# 800U-R3N3_IB_LED_V1_0.net
KiCad netlist of a schematic drawn in Altium Designer
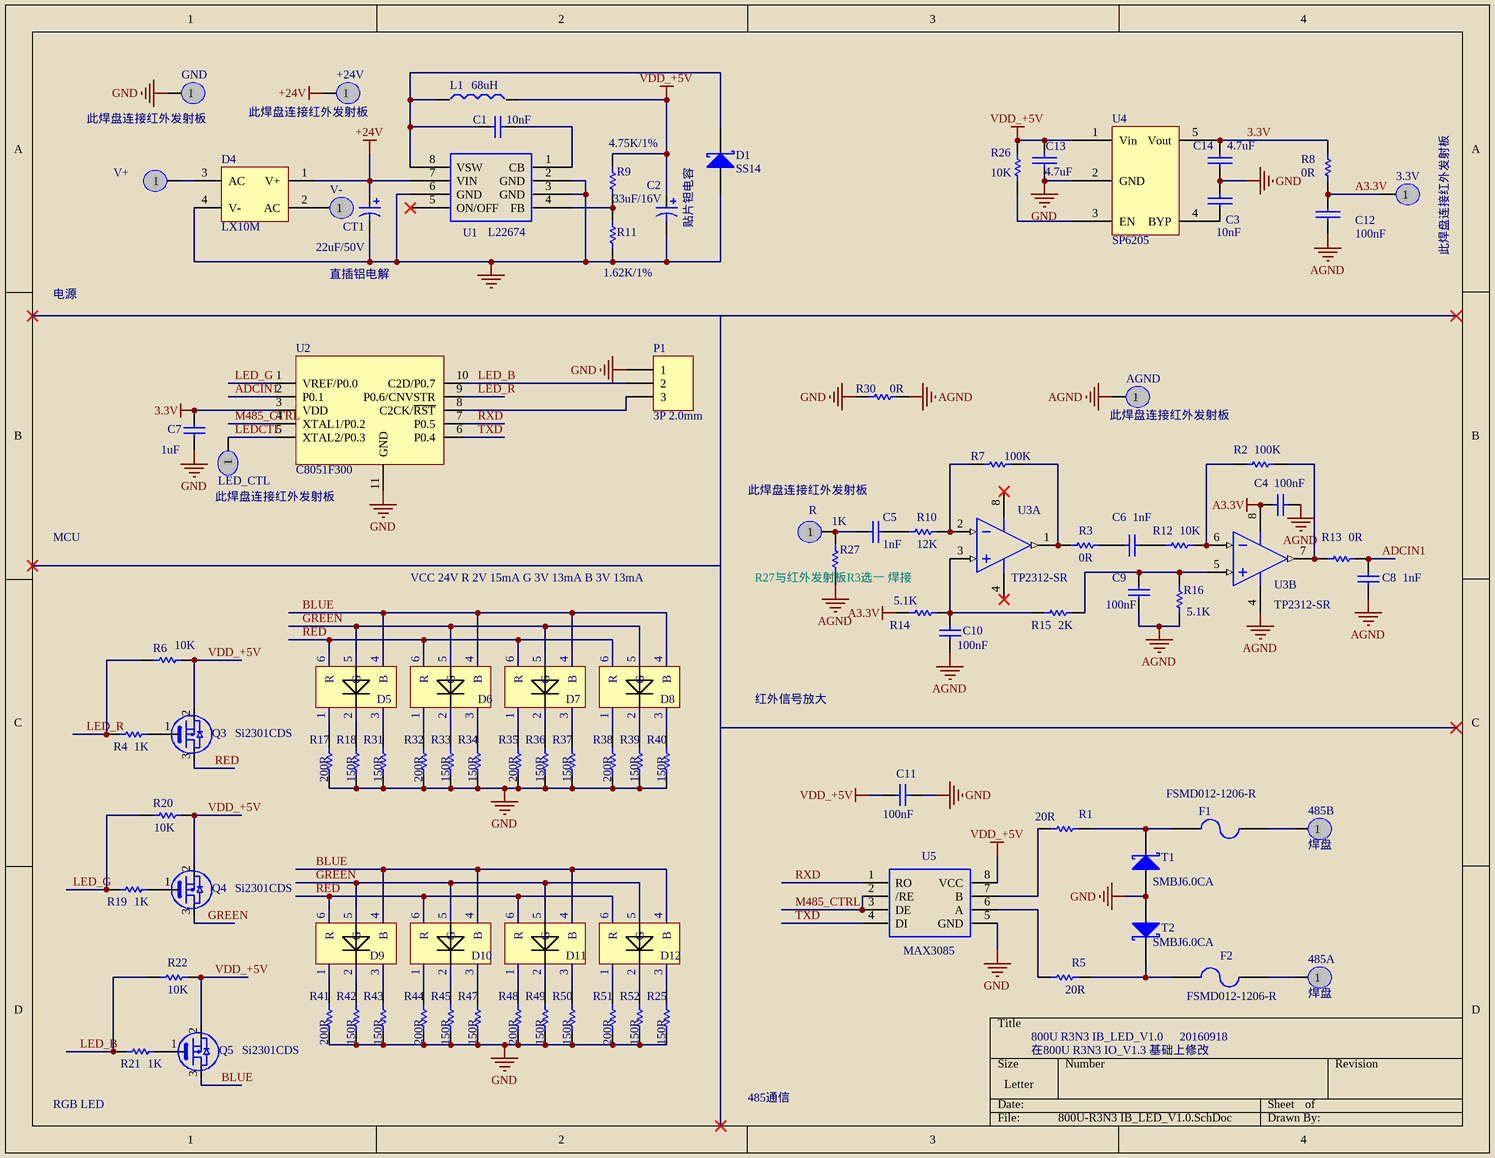
[diagram p0: 800U-R3N3 IB_LED_V1.0.SchDoc]

(export (version "E")
  (design (tool "Eeschema 10.0.6"))
  (components
    (comp (ref "+24V")
      (value "~")
      (footprint "HOLE_SMD")
      (fields (field (name "ALTIUM_UNNAMED_1") "此焊盘连接红外发射板"))
      (libsource (lib "MODBUS_V1.0") (part "焊盘"))
    )
    (comp (ref "3.3V")
      (value "~")
      (footprint "HOLE_SMD")
      (fields (field (name "ALTIUM_UNNAMED_1") "此焊盘连接红外发射板"))
      (libsource (lib "MODBUS_V1.0") (part "焊盘"))
    )
    (comp (ref "485A") (value "焊盘") (footprint "HOLE_SMD") (libsource (lib "MODBUS_V1.0") (part "焊盘")))
    (comp (ref "485B") (value "焊盘") (footprint "HOLE_SMD") (libsource (lib "MODBUS_V1.0") (part "焊盘")))
    (comp (ref "AGND")
      (value "~")
      (footprint "HOLE_SMD")
      (fields (field (name "ALTIUM_UNNAMED_1") "此焊盘连接红外发射板"))
      (libsource (lib "MODBUS_V1.0") (part "焊盘"))
    )
    (comp (ref "C1")
      (value "10nF")
      (footprint "C0603")
      (description "Capacitor")
      (fields (field (name "PUBLISHER") "Altium Limited"))
      (libsource (lib "*") (part "Cap"))
    )
    (comp (ref "C2")
      (value "33uF/16V")
      (footprint "CT3528")
      (description "Polarized Capacitor (Radial)")
      (fields (field (name "KIND") "贴片钽电容"))
      (libsource (lib "*") (part "Cap Pol1"))
    )
    (comp (ref "C3")
      (value "10nF")
      (footprint "C0603")
      (description "Capacitor")
      (libsource (lib "*") (part "CAP"))
    )
    (comp (ref "C4")
      (value "100nF")
      (footprint "C0603")
      (description "Capacitor")
      (fields (field (name "PUBLISHER") "Altium Limited"))
      (libsource (lib "TMJD1.0") (part "Cap"))
    )
    (comp (ref "C5")
      (value "1nF")
      (footprint "C0603")
      (description "Capacitor")
      (fields (field (name "PUBLISHER") "Altium Limited"))
      (libsource (lib "TMJD1.0") (part "Cap"))
    )
    (comp (ref "C6")
      (value "1nF")
      (footprint "C0603")
      (description "Capacitor")
      (fields (field (name "PUBLISHER") "Altium Limited"))
      (libsource (lib "TMJD1.0") (part "Cap"))
    )
    (comp (ref "C7")
      (value "1uF")
      (footprint "C0603")
      (description "贴片电容")
      (fields (field (name "PUBLISHER") "Altium Limited"))
      (libsource (lib "TMJD1.0") (part "Cap"))
    )
    (comp (ref "C8")
      (value "1nF")
      (footprint "C0603")
      (description "Capacitor")
      (fields (field (name "PUBLISHER") "Altium Limited"))
      (libsource (lib "TMJD1.0") (part "Cap"))
    )
    (comp (ref "C9")
      (value "100nF")
      (footprint "C0603")
      (description "Capacitor")
      (fields (field (name "PUBLISHER") "Altium Limited"))
      (libsource (lib "TMJD1.0") (part "Cap"))
    )
    (comp (ref "C10")
      (value "100nF")
      (footprint "C0603")
      (description "Capacitor")
      (fields (field (name "PUBLISHER") "Altium Limited"))
      (libsource (lib "TMJD1.0") (part "Cap"))
    )
    (comp (ref "C11")
      (value "100nF")
      (footprint "C0603")
      (description "贴片陶瓷电容")
      (libsource (lib "Miscellaneous Devices") (part "Cap"))
    )
    (comp (ref "C12")
      (value "100nF")
      (footprint "C0603")
      (description "Capacitor")
      (libsource (lib "*") (part "CAP"))
    )
    (comp (ref "C13")
      (value "4.7uF")
      (footprint "C0603")
      (description "Capacitor")
      (libsource (lib "*") (part "CAP"))
    )
    (comp (ref "C14")
      (value "4.7uF")
      (footprint "C0603")
      (description "Capacitor")
      (libsource (lib "*") (part "CAP"))
    )
    (comp (ref "CT1")
      (value "22uF/50V")
      (footprint "RB0.1")
      (description "Polarized Capacitor (Radial)")
      (fields (field (name "KIND") "直插铝电解"))
      (libsource (lib "*") (part "Cap Pol1"))
    )
    (comp (ref "D1") (value "SS14") (footprint "SMB") (libsource (lib "*") (part "SMBJ6.0CA")))
    (comp (ref "D4")
      (value "LX10M")
      (footprint "桥堆 3.8*3.5")
      (description "贴片桥堆")
      (libsource (lib "Miscellaneous Devices") (part "Bridge2"))
    )
    (comp (ref "D5")
      (value "5050RGB")
      (footprint "5050RGB")
      (description "RBG发光管")
      (libsource (lib "MODBUS_V1.0") (part "5050RGB"))
    )
    (comp (ref "D6")
      (value "5050RGB")
      (footprint "5050RGB")
      (description "RBG发光管")
      (libsource (lib "MODBUS_V1.0") (part "5050RGB"))
    )
    (comp (ref "D7")
      (value "5050RGB")
      (footprint "5050RGB")
      (description "RBG发光管")
      (libsource (lib "MODBUS_V1.0") (part "5050RGB"))
    )
    (comp (ref "D8")
      (value "5050RGB")
      (footprint "5050RGB")
      (description "RBG发光管")
      (libsource (lib "MODBUS_V1.0") (part "5050RGB"))
    )
    (comp (ref "D9")
      (value "5050RGB")
      (footprint "5050RGB")
      (description "RBG发光管")
      (libsource (lib "MODBUS_V1.0") (part "5050RGB"))
    )
    (comp (ref "D10")
      (value "5050RGB")
      (footprint "5050RGB")
      (description "RBG发光管")
      (libsource (lib "MODBUS_V1.0") (part "5050RGB"))
    )
    (comp (ref "D11")
      (value "5050RGB")
      (footprint "5050RGB")
      (description "RBG发光管")
      (libsource (lib "MODBUS_V1.0") (part "5050RGB"))
    )
    (comp (ref "D12")
      (value "5050RGB")
      (footprint "5050RGB")
      (description "RBG发光管")
      (libsource (lib "MODBUS_V1.0") (part "5050RGB"))
    )
    (comp (ref "F1")
      (value "FSMD012-1206-R")
      (footprint "1206")
      (description "可恢复保险丝")
      (libsource (lib "Miscellaneous Devices") (part "Fuse 2"))
    )
    (comp (ref "F2")
      (value "FSMD012-1206-R")
      (footprint "1206")
      (description "可恢复保险丝")
      (libsource (lib "Miscellaneous Devices") (part "Fuse 2"))
    )
    (comp (ref "GND")
      (value "~")
      (footprint "HOLE_SMD")
      (fields (field (name "ALTIUM_UNNAMED_1") "此焊盘连接红外发射板"))
      (libsource (lib "MODBUS_V1.0") (part "焊盘"))
    )
    (comp (ref "L1") (value "68uH") (footprint "L-6X6") (libsource (lib "*") (part "电感")))
    (comp (ref "LED_CTL")
      (value "~")
      (footprint "HOLE_SMD")
      (fields (field (name "ALTIUM_UNNAMED_1") "此焊盘连接红外发射板"))
      (libsource (lib "MODBUS_V1.0") (part "焊盘"))
    )
    (comp (ref "P1")
      (value "3P 2.0mm")
      (footprint "SIP3")
      (description "插座")
      (fields (field (name "PUBLISHER") "Altium Limited"))
      (libsource (lib "Miscellaneous Connectors") (part "MHDR1X3"))
    )
    (comp (ref "Q3")
      (value "Si2301CDS")
      (footprint "SOT-23")
      (description "贴片MOS管")
      (libsource (lib "BATTERY") (part "P-MOSFET"))
    )
    (comp (ref "Q4")
      (value "Si2301CDS")
      (footprint "SOT-23")
      (description "贴片MOS管")
      (libsource (lib "BATTERY") (part "P-MOSFET"))
    )
    (comp (ref "Q5")
      (value "Si2301CDS")
      (footprint "SOT-23")
      (description "贴片MOS管")
      (libsource (lib "BATTERY") (part "P-MOSFET"))
    )
    (comp (ref "R")
      (value "~")
      (footprint "HOLE_SMD")
      (fields (field (name "ALTIUM_UNNAMED_1") "此焊盘连接红外发射板"))
      (libsource (lib "MODBUS_V1.0") (part "焊盘"))
    )
    (comp (ref "R1")
      (value "20R")
      (footprint "2010")
      (description "贴片电阻")
      (libsource (lib "Miscellaneous Devices") (part "Res Semi"))
    )
    (comp (ref "R2")
      (value "100K")
      (footprint "R0603")
      (description "Semiconductor Resistor")
      (libsource (lib "Miscellaneous Devices") (part "Res Semi"))
    )
    (comp (ref "R3")
      (value "0R")
      (footprint "R0603")
      (description "Semiconductor Resistor")
      (libsource (lib "Miscellaneous Devices") (part "Res Semi"))
    )
    (comp (ref "R4")
      (value "1K")
      (footprint "R0603")
      (description "贴片电阻")
      (libsource (lib "Miscellaneous Devices") (part "Res Semi"))
    )
    (comp (ref "R5")
      (value "20R")
      (footprint "2010")
      (description "贴片电阻")
      (libsource (lib "Miscellaneous Devices") (part "Res Semi"))
    )
    (comp (ref "R6")
      (value "10K")
      (footprint "R0603")
      (description "贴片电阻")
      (libsource (lib "Miscellaneous Devices") (part "Res Semi"))
    )
    (comp (ref "R7")
      (value "100K")
      (footprint "R0603")
      (description "Semiconductor Resistor")
      (libsource (lib "Miscellaneous Devices") (part "Res Semi"))
    )
    (comp (ref "R8")
      (value "0R")
      (footprint "R0603")
      (description "Resistor")
      (fields (field (name "PUBLISHER") "Altium Limited"))
      (libsource (lib "*") (part "Res1"))
    )
    (comp (ref "R9")
      (value "4.75K/1%")
      (footprint "R0603")
      (description "Semiconductor Resistor")
      (fields (field (name "PUBLISHER") "Altium Limited"))
      (libsource (lib "*") (part "Res Semi"))
    )
    (comp (ref "R10")
      (value "12K")
      (footprint "R0603")
      (description "Semiconductor Resistor")
      (libsource (lib "Miscellaneous Devices") (part "Res Semi"))
    )
    (comp (ref "R11")
      (value "1.62K/1%")
      (footprint "R0603")
      (description "Semiconductor Resistor")
      (fields (field (name "PUBLISHER") "Altium Limited"))
      (libsource (lib "*") (part "Res Semi"))
    )
    (comp (ref "R12")
      (value "10K")
      (footprint "R0603")
      (description "Semiconductor Resistor")
      (libsource (lib "Miscellaneous Devices") (part "Res Semi"))
    )
    (comp (ref "R13")
      (value "0R")
      (footprint "R0603")
      (description "Semiconductor Resistor")
      (libsource (lib "Miscellaneous Devices") (part "Res Semi"))
    )
    (comp (ref "R14")
      (value "5.1K")
      (footprint "R0603")
      (description "Semiconductor Resistor")
      (libsource (lib "Miscellaneous Devices") (part "Res Semi"))
    )
    (comp (ref "R15")
      (value "2K")
      (footprint "R0603")
      (description "Semiconductor Resistor")
      (libsource (lib "Miscellaneous Devices") (part "Res Semi"))
    )
    (comp (ref "R16")
      (value "5.1K")
      (footprint "R0603")
      (description "Semiconductor Resistor")
      (libsource (lib "Miscellaneous Devices") (part "Res Semi"))
    )
    (comp (ref "R17")
      (value "200R")
      (footprint "0805")
      (description "贴片电阻")
      (libsource (lib "Miscellaneous Devices") (part "Res Semi"))
    )
    (comp (ref "R18")
      (value "150R")
      (footprint "0805")
      (description "贴片电阻")
      (libsource (lib "Miscellaneous Devices") (part "Res Semi"))
    )
    (comp (ref "R19")
      (value "1K")
      (footprint "R0603")
      (description "贴片电阻")
      (libsource (lib "Miscellaneous Devices") (part "Res Semi"))
    )
    (comp (ref "R20")
      (value "10K")
      (footprint "R0603")
      (description "贴片电阻")
      (libsource (lib "Miscellaneous Devices") (part "Res Semi"))
    )
    (comp (ref "R21")
      (value "1K")
      (footprint "R0603")
      (description "贴片电阻")
      (libsource (lib "Miscellaneous Devices") (part "Res Semi"))
    )
    (comp (ref "R22")
      (value "10K")
      (footprint "R0603")
      (description "贴片电阻")
      (libsource (lib "Miscellaneous Devices") (part "Res Semi"))
    )
    (comp (ref "R25")
      (value "150R")
      (footprint "0805")
      (description "贴片电阻")
      (libsource (lib "Miscellaneous Devices") (part "Res Semi"))
    )
    (comp (ref "R26")
      (value "10K")
      (footprint "R0603")
      (description "Resistor")
      (fields (field (name "PUBLISHER") "Altium Limited"))
      (libsource (lib "*") (part "Res1"))
    )
    (comp (ref "R27")
      (value "1K")
      (footprint "R0603")
      (description "Semiconductor Resistor")
      (fields (field (name "ALTIUM_UNNAMED_1") "R27与红外发射板R3选一 焊接"))
      (libsource (lib "Miscellaneous Devices") (part "Res Semi"))
    )
    (comp (ref "R30")
      (value "0R")
      (footprint "R0603")
      (description "Semiconductor Resistor")
      (libsource (lib "Miscellaneous Devices") (part "Res Semi"))
    )
    (comp (ref "R31")
      (value "150R")
      (footprint "0805")
      (description "贴片电阻")
      (libsource (lib "Miscellaneous Devices") (part "Res Semi"))
    )
    (comp (ref "R32")
      (value "200R")
      (footprint "0805")
      (description "贴片电阻")
      (libsource (lib "Miscellaneous Devices") (part "Res Semi"))
    )
    (comp (ref "R33")
      (value "150R")
      (footprint "0805")
      (description "贴片电阻")
      (libsource (lib "Miscellaneous Devices") (part "Res Semi"))
    )
    (comp (ref "R34")
      (value "150R")
      (footprint "0805")
      (description "贴片电阻")
      (libsource (lib "Miscellaneous Devices") (part "Res Semi"))
    )
    (comp (ref "R35")
      (value "200R")
      (footprint "0805")
      (description "贴片电阻")
      (libsource (lib "Miscellaneous Devices") (part "Res Semi"))
    )
    (comp (ref "R36")
      (value "150R")
      (footprint "0805")
      (description "贴片电阻")
      (libsource (lib "Miscellaneous Devices") (part "Res Semi"))
    )
    (comp (ref "R37")
      (value "150R")
      (footprint "0805")
      (description "贴片电阻")
      (libsource (lib "Miscellaneous Devices") (part "Res Semi"))
    )
    (comp (ref "R38")
      (value "200R")
      (footprint "0805")
      (description "贴片电阻")
      (libsource (lib "Miscellaneous Devices") (part "Res Semi"))
    )
    (comp (ref "R39")
      (value "150R")
      (footprint "0805")
      (description "贴片电阻")
      (libsource (lib "Miscellaneous Devices") (part "Res Semi"))
    )
    (comp (ref "R40")
      (value "150R")
      (footprint "0805")
      (description "贴片电阻")
      (libsource (lib "Miscellaneous Devices") (part "Res Semi"))
    )
    (comp (ref "R41")
      (value "200R")
      (footprint "0805")
      (description "贴片电阻")
      (libsource (lib "Miscellaneous Devices") (part "Res Semi"))
    )
    (comp (ref "R42")
      (value "150R")
      (footprint "0805")
      (description "贴片电阻")
      (libsource (lib "Miscellaneous Devices") (part "Res Semi"))
    )
    (comp (ref "R43")
      (value "150R")
      (footprint "0805")
      (description "贴片电阻")
      (libsource (lib "Miscellaneous Devices") (part "Res Semi"))
    )
    (comp (ref "R44")
      (value "200R")
      (footprint "0805")
      (description "贴片电阻")
      (libsource (lib "Miscellaneous Devices") (part "Res Semi"))
    )
    (comp (ref "R45")
      (value "150R")
      (footprint "0805")
      (description "贴片电阻")
      (libsource (lib "Miscellaneous Devices") (part "Res Semi"))
    )
    (comp (ref "R47")
      (value "150R")
      (footprint "0805")
      (description "贴片电阻")
      (libsource (lib "Miscellaneous Devices") (part "Res Semi"))
    )
    (comp (ref "R48")
      (value "200R")
      (footprint "0805")
      (description "贴片电阻")
      (libsource (lib "Miscellaneous Devices") (part "Res Semi"))
    )
    (comp (ref "R49")
      (value "150R")
      (footprint "0805")
      (description "贴片电阻")
      (libsource (lib "Miscellaneous Devices") (part "Res Semi"))
    )
    (comp (ref "R50")
      (value "150R")
      (footprint "0805")
      (description "贴片电阻")
      (libsource (lib "Miscellaneous Devices") (part "Res Semi"))
    )
    (comp (ref "R51")
      (value "200R")
      (footprint "0805")
      (description "贴片电阻")
      (libsource (lib "Miscellaneous Devices") (part "Res Semi"))
    )
    (comp (ref "R52")
      (value "150R")
      (footprint "0805")
      (description "贴片电阻")
      (libsource (lib "Miscellaneous Devices") (part "Res Semi"))
    )
    (comp (ref "T1")
      (value "~")
      (footprint "HSMA")
      (description "TVS管")
      (fields (field (name "型号") "SMBJ6.0CA"))
      (libsource (lib "MODBUS_V1.0") (part "SMBJ6.0CA"))
    )
    (comp (ref "T2")
      (value "~")
      (footprint "HSMA")
      (description "TVS管")
      (fields (field (name "型号") "SMBJ6.0CA"))
      (libsource (lib "MODBUS_V1.0") (part "SMBJ6.0CA"))
    )
    (comp (ref "U1") (value "L22674") (footprint "SO-1.27-9/4.0") (libsource (lib "*") (part "2674")))
    (comp (ref "U2")
      (value "C8051F300")
      (footprint "QFN-11")
      (description "贴片芯片")
      (libsource (lib "集成块") (part "PIC16C505"))
    )
    (comp (ref "U3")
      (value "TP2312-SR")
      (footprint "SO-8")
      (description "Dual Low Noise, Audio Amplifier")
      (fields (field (name "PUBLISHER") "Altium Limited"))
      (libsource (lib "Motorola Amplifier Audio Amplifier") (part "LM833D"))
    )
    (comp (ref "U4")
      (value "SP6205")
      (footprint "SOT-23-5")
      (libsource (lib "MODBUS_V1.0") (part "SP6203/SP6205"))
    )
    (comp (ref "U5")
      (value "MAX3085")
      (footprint "SO-1.27-8/4.0")
      (description "贴片芯片")
      (libsource (lib "*") (part "MAX_485"))
    )
    (comp (ref "V+") (value "~") (footprint "HOLE_SMD") (libsource (lib "MODBUS_V1.0") (part "焊盘")))
    (comp (ref "V-") (value "~") (footprint "HOLE_SMD") (libsource (lib "MODBUS_V1.0") (part "焊盘")))
  )
  (nets
    (net (code "1") (name "+24V") (class "Default")
      (node (ref "+24V") (pin "1") (pinfunction "1_1") (pintype "passive"))
      (node (ref "CT1") (pin "1") (pinfunction "1_1") (pintype "passive"))
      (node (ref "D4") (pin "1") (pinfunction "V+_1") (pintype "passive"))
      (node (ref "U1") (pin "7") (pinfunction "VIN_7") (pintype "passive"))
    )
    (net (code "2") (name "/ADCIN1") (class "Default")
      (node (ref "C8") (pin "2") (pinfunction "2_2") (pintype "passive"))
      (node (ref "R13") (pin "2") (pinfunction "2_2") (pintype "passive"))
      (node (ref "U2") (pin "2") (pinfunction "P0.1_2") (pintype "passive"))
    )
    (net (code "3") (name "/BLUE") (class "Default")
      (node (ref "D10") (pin "4") (pinfunction "B_4") (pintype "passive"))
      (node (ref "D11") (pin "4") (pinfunction "B_4") (pintype "passive"))
      (node (ref "D12") (pin "4") (pinfunction "B_4") (pintype "passive"))
      (node (ref "D5") (pin "4") (pinfunction "B_4") (pintype "passive"))
      (node (ref "D6") (pin "4") (pinfunction "B_4") (pintype "passive"))
      (node (ref "D7") (pin "4") (pinfunction "B_4") (pintype "passive"))
      (node (ref "D8") (pin "4") (pinfunction "B_4") (pintype "passive"))
      (node (ref "D9") (pin "4") (pinfunction "B_4") (pintype "passive"))
      (node (ref "Q5") (pin "3") (pinfunction "D_3") (pintype "passive"))
    )
    (net (code "4") (name "/GREEN") (class "Default")
      (node (ref "D10") (pin "5") (pinfunction "G_5") (pintype "passive"))
      (node (ref "D11") (pin "5") (pinfunction "G_5") (pintype "passive"))
      (node (ref "D12") (pin "5") (pinfunction "G_5") (pintype "passive"))
      (node (ref "D5") (pin "5") (pinfunction "G_5") (pintype "passive"))
      (node (ref "D6") (pin "5") (pinfunction "G_5") (pintype "passive"))
      (node (ref "D7") (pin "5") (pinfunction "G_5") (pintype "passive"))
      (node (ref "D8") (pin "5") (pinfunction "G_5") (pintype "passive"))
      (node (ref "D9") (pin "5") (pinfunction "G_5") (pintype "passive"))
      (node (ref "Q4") (pin "3") (pinfunction "D_3") (pintype "passive"))
    )
    (net (code "5") (name "/LEDCTL") (class "Default")
      (node (ref "LED_CTL") (pin "1") (pinfunction "1_1") (pintype "passive"))
      (node (ref "U2") (pin "5") (pinfunction "XTAL2/P0.3_5") (pintype "passive"))
    )
    (net (code "6") (name "/LED_B") (class "Default")
      (node (ref "P1") (pin "2") (pinfunction "2_2") (pintype "passive"))
      (node (ref "R21") (pin "2") (pinfunction "2_2") (pintype "passive"))
      (node (ref "R22") (pin "2") (pinfunction "2_2") (pintype "passive"))
      (node (ref "U2") (pin "10") (pinfunction "C2D/P0.7_10") (pintype "passive"))
    )
    (net (code "7") (name "/LED_G") (class "Default")
      (node (ref "R19") (pin "2") (pinfunction "2_2") (pintype "passive"))
      (node (ref "R20") (pin "2") (pinfunction "2_2") (pintype "passive"))
      (node (ref "U2") (pin "1") (pinfunction "VREF/P0.0_1") (pintype "passive"))
    )
    (net (code "8") (name "/LED_R") (class "Default")
      (node (ref "R4") (pin "2") (pinfunction "2_2") (pintype "passive"))
      (node (ref "R6") (pin "2") (pinfunction "2_2") (pintype "passive"))
      (node (ref "U2") (pin "9") (pinfunction "P0.6/CNVSTR_9") (pintype "passive"))
    )
    (net (code "9") (name "/M485_CTRL") (class "Default")
      (node (ref "U2") (pin "4") (pinfunction "XTAL1/P0.2_4") (pintype "passive"))
      (node (ref "U5") (pin "2") (pinfunction "/RE_2") (pintype "passive"))
      (node (ref "U5") (pin "3") (pinfunction "DE_3") (pintype "passive"))
    )
    (net (code "10") (name "/RED") (class "Default")
      (node (ref "D10") (pin "6") (pinfunction "R_6") (pintype "passive"))
      (node (ref "D11") (pin "6") (pinfunction "R_6") (pintype "passive"))
      (node (ref "D12") (pin "6") (pinfunction "R_6") (pintype "passive"))
      (node (ref "D5") (pin "6") (pinfunction "R_6") (pintype "passive"))
      (node (ref "D6") (pin "6") (pinfunction "R_6") (pintype "passive"))
      (node (ref "D7") (pin "6") (pinfunction "R_6") (pintype "passive"))
      (node (ref "D8") (pin "6") (pinfunction "R_6") (pintype "passive"))
      (node (ref "D9") (pin "6") (pinfunction "R_6") (pintype "passive"))
      (node (ref "Q3") (pin "3") (pinfunction "D_3") (pintype "passive"))
    )
    (net (code "11") (name "/RXD") (class "Default")
      (node (ref "U2") (pin "7") (pinfunction "P0.5_7") (pintype "passive"))
      (node (ref "U5") (pin "1") (pinfunction "RO_1") (pintype "passive"))
    )
    (net (code "12") (name "/TXD") (class "Default")
      (node (ref "U2") (pin "6") (pinfunction "P0.4_6") (pintype "passive"))
      (node (ref "U5") (pin "4") (pinfunction "DI_4") (pintype "passive"))
    )
    (net (code "13") (name "3.3V") (class "Default")
      (node (ref "C14") (pin "1") (pinfunction "1_1") (pintype "passive"))
      (node (ref "C7") (pin "1") (pinfunction "1_1") (pintype "passive"))
      (node (ref "R8") (pin "1") (pinfunction "1_1") (pintype "passive"))
      (node (ref "U2") (pin "3") (pinfunction "VDD_3") (pintype "passive"))
      (node (ref "U4") (pin "5") (pinfunction "Vout_5") (pintype "passive"))
    )
    (net (code "14") (name "A3.3V") (class "Default")
      (node (ref "3.3V") (pin "1") (pinfunction "1_1") (pintype "passive"))
      (node (ref "C12") (pin "2") (pinfunction "2_2") (pintype "passive"))
      (node (ref "C4") (pin "1") (pinfunction "1_1") (pintype "passive"))
      (node (ref "R14") (pin "1") (pinfunction "1_1") (pintype "passive"))
      (node (ref "R8") (pin "2") (pinfunction "2_2") (pintype "passive"))
      (node (ref "U3") (pin "8") (pinfunction "VCC_8") (pintype "power_in"))
    )
    (net (code "15") (name "AGND") (class "Default")
      (node (ref "AGND") (pin "1") (pinfunction "1_1") (pintype "passive"))
      (node (ref "C10") (pin "2") (pinfunction "2_2") (pintype "passive"))
      (node (ref "C12") (pin "1") (pinfunction "1_1") (pintype "passive"))
      (node (ref "C4") (pin "2") (pinfunction "2_2") (pintype "passive"))
      (node (ref "C8") (pin "1") (pinfunction "1_1") (pintype "passive"))
      (node (ref "C9") (pin "2") (pinfunction "2_2") (pintype "passive"))
      (node (ref "R16") (pin "1") (pinfunction "1_1") (pintype "passive"))
      (node (ref "R27") (pin "2") (pinfunction "2_2") (pintype "passive"))
      (node (ref "R30") (pin "2") (pinfunction "2_2") (pintype "passive"))
      (node (ref "U3") (pin "4") (pinfunction "VEE_4") (pintype "power_in"))
    )
    (net (code "16") (name "GND") (class "Default")
      (node (ref "C11") (pin "1") (pinfunction "1_1") (pintype "passive"))
      (node (ref "C13") (pin "2") (pinfunction "2_2") (pintype "passive"))
      (node (ref "C14") (pin "2") (pinfunction "2_2") (pintype "passive"))
      (node (ref "C2") (pin "2") (pinfunction "2_2") (pintype "passive"))
      (node (ref "C3") (pin "2") (pinfunction "2_2") (pintype "passive"))
      (node (ref "C7") (pin "2") (pinfunction "2_2") (pintype "passive"))
      (node (ref "CT1") (pin "2") (pinfunction "2_2") (pintype "passive"))
      (node (ref "D1") (pin "1") (pinfunction "A_1") (pintype "passive"))
      (node (ref "D4") (pin "4") (pinfunction "V-_4") (pintype "passive"))
      (node (ref "GND") (pin "1") (pinfunction "1_1") (pintype "passive"))
      (node (ref "P1") (pin "1") (pinfunction "1_1") (pintype "passive"))
      (node (ref "R11") (pin "1") (pinfunction "1_1") (pintype "passive"))
      (node (ref "R17") (pin "1") (pinfunction "1_1") (pintype "passive"))
      (node (ref "R18") (pin "1") (pinfunction "1_1") (pintype "passive"))
      (node (ref "R25") (pin "1") (pinfunction "1_1") (pintype "passive"))
      (node (ref "R30") (pin "1") (pinfunction "1_1") (pintype "passive"))
      (node (ref "R31") (pin "1") (pinfunction "1_1") (pintype "passive"))
      (node (ref "R32") (pin "1") (pinfunction "1_1") (pintype "passive"))
      (node (ref "R33") (pin "1") (pinfunction "1_1") (pintype "passive"))
      (node (ref "R34") (pin "1") (pinfunction "1_1") (pintype "passive"))
      (node (ref "R35") (pin "1") (pinfunction "1_1") (pintype "passive"))
      (node (ref "R36") (pin "1") (pinfunction "1_1") (pintype "passive"))
      (node (ref "R37") (pin "1") (pinfunction "1_1") (pintype "passive"))
      (node (ref "R38") (pin "1") (pinfunction "1_1") (pintype "passive"))
      (node (ref "R39") (pin "1") (pinfunction "1_1") (pintype "passive"))
      (node (ref "R40") (pin "1") (pinfunction "1_1") (pintype "passive"))
      (node (ref "R41") (pin "1") (pinfunction "1_1") (pintype "passive"))
      (node (ref "R42") (pin "1") (pinfunction "1_1") (pintype "passive"))
      (node (ref "R43") (pin "1") (pinfunction "1_1") (pintype "passive"))
      (node (ref "R44") (pin "1") (pinfunction "1_1") (pintype "passive"))
      (node (ref "R45") (pin "1") (pinfunction "1_1") (pintype "passive"))
      (node (ref "R47") (pin "1") (pinfunction "1_1") (pintype "passive"))
      (node (ref "R48") (pin "1") (pinfunction "1_1") (pintype "passive"))
      (node (ref "R49") (pin "1") (pinfunction "1_1") (pintype "passive"))
      (node (ref "R50") (pin "1") (pinfunction "1_1") (pintype "passive"))
      (node (ref "R51") (pin "1") (pinfunction "1_1") (pintype "passive"))
      (node (ref "R52") (pin "1") (pinfunction "1_1") (pintype "passive"))
      (node (ref "T1") (pin "1") (pinfunction "A_1") (pintype "passive"))
      (node (ref "T2") (pin "1") (pinfunction "A_1") (pintype "passive"))
      (node (ref "U1") (pin "2") (pinfunction "GND_2") (pintype "passive"))
      (node (ref "U1") (pin "3") (pinfunction "GND_3") (pintype "passive"))
      (node (ref "U1") (pin "6") (pinfunction "GND_6") (pintype "passive"))
      (node (ref "U2") (pin "11") (pinfunction "GND_11") (pintype "passive"))
      (node (ref "U4") (pin "2") (pinfunction "GND_2") (pintype "passive"))
      (node (ref "U5") (pin "5") (pinfunction "GND_5") (pintype "passive"))
    )
    (net (code "17") (name "Net-(485A-Pad1)") (class "Default")
      (node (ref "485A") (pin "1") (pinfunction "1_1") (pintype "passive"))
      (node (ref "F2") (pin "2") (pinfunction "2_2") (pintype "passive"))
    )
    (net (code "18") (name "Net-(485B-Pad1)") (class "Default")
      (node (ref "485B") (pin "1") (pinfunction "1_1") (pintype "passive"))
      (node (ref "F1") (pin "2") (pinfunction "2_2") (pintype "passive"))
    )
    (net (code "19") (name "Net-(C5-Pad1)") (class "Default")
      (node (ref "C5") (pin "1") (pinfunction "1_1") (pintype "passive"))
      (node (ref "R") (pin "1") (pinfunction "1_1") (pintype "passive"))
      (node (ref "R27") (pin "1") (pinfunction "1_1") (pintype "passive"))
    )
    (net (code "20") (name "Net-(C5-Pad2)") (class "Default")
      (node (ref "C5") (pin "2") (pinfunction "2_2") (pintype "passive"))
      (node (ref "R10") (pin "1") (pinfunction "1_1") (pintype "passive"))
    )
    (net (code "21") (name "Net-(C6-Pad1)") (class "Default")
      (node (ref "C6") (pin "1") (pinfunction "1_1") (pintype "passive"))
      (node (ref "R3") (pin "2") (pinfunction "2_2") (pintype "passive"))
    )
    (net (code "22") (name "Net-(C6-Pad2)") (class "Default")
      (node (ref "C6") (pin "2") (pinfunction "2_2") (pintype "passive"))
      (node (ref "R12") (pin "1") (pinfunction "1_1") (pintype "passive"))
    )
    (net (code "23") (name "Net-(D1-K)") (class "Default")
      (node (ref "C1") (pin "2") (pinfunction "2_2") (pintype "passive"))
      (node (ref "D1") (pin "2") (pinfunction "K_2") (pintype "passive"))
      (node (ref "L1") (pin "1") (pinfunction "1_1") (pintype "passive"))
      (node (ref "U1") (pin "8") (pinfunction "VSW_8") (pintype "passive"))
    )
    (net (code "24") (name "Net-(D4-AC-Pad2)") (class "Default")
      (node (ref "D4") (pin "2") (pinfunction "AC_2") (pintype "passive"))
      (node (ref "V-") (pin "1") (pinfunction "1_1") (pintype "passive"))
    )
    (net (code "25") (name "Net-(D4-AC-Pad3)") (class "Default")
      (node (ref "D4") (pin "3") (pinfunction "AC_3") (pintype "passive"))
      (node (ref "V+") (pin "1") (pinfunction "1_1") (pintype "passive"))
    )
    (net (code "26") (name "Net-(D5-Pad1)") (class "Default")
      (node (ref "D5") (pin "1") (pintype "passive"))
      (node (ref "R17") (pin "2") (pinfunction "2_2") (pintype "passive"))
    )
    (net (code "27") (name "Net-(D5-Pad2)") (class "Default")
      (node (ref "D5") (pin "2") (pintype "passive"))
      (node (ref "R18") (pin "2") (pinfunction "2_2") (pintype "passive"))
    )
    (net (code "28") (name "Net-(D5-Pad3)") (class "Default")
      (node (ref "D5") (pin "3") (pintype "passive"))
      (node (ref "R31") (pin "2") (pinfunction "2_2") (pintype "passive"))
    )
    (net (code "29") (name "Net-(D6-Pad1)") (class "Default")
      (node (ref "D6") (pin "1") (pintype "passive"))
      (node (ref "R32") (pin "2") (pinfunction "2_2") (pintype "passive"))
    )
    (net (code "30") (name "Net-(D6-Pad2)") (class "Default")
      (node (ref "D6") (pin "2") (pintype "passive"))
      (node (ref "R33") (pin "2") (pinfunction "2_2") (pintype "passive"))
    )
    (net (code "31") (name "Net-(D6-Pad3)") (class "Default")
      (node (ref "D6") (pin "3") (pintype "passive"))
      (node (ref "R34") (pin "2") (pinfunction "2_2") (pintype "passive"))
    )
    (net (code "32") (name "Net-(D7-Pad1)") (class "Default")
      (node (ref "D7") (pin "1") (pintype "passive"))
      (node (ref "R35") (pin "2") (pinfunction "2_2") (pintype "passive"))
    )
    (net (code "33") (name "Net-(D7-Pad2)") (class "Default")
      (node (ref "D7") (pin "2") (pintype "passive"))
      (node (ref "R36") (pin "2") (pinfunction "2_2") (pintype "passive"))
    )
    (net (code "34") (name "Net-(D7-Pad3)") (class "Default")
      (node (ref "D7") (pin "3") (pintype "passive"))
      (node (ref "R37") (pin "2") (pinfunction "2_2") (pintype "passive"))
    )
    (net (code "35") (name "Net-(D8-Pad1)") (class "Default")
      (node (ref "D8") (pin "1") (pintype "passive"))
      (node (ref "R38") (pin "2") (pinfunction "2_2") (pintype "passive"))
    )
    (net (code "36") (name "Net-(D8-Pad2)") (class "Default")
      (node (ref "D8") (pin "2") (pintype "passive"))
      (node (ref "R39") (pin "2") (pinfunction "2_2") (pintype "passive"))
    )
    (net (code "37") (name "Net-(D8-Pad3)") (class "Default")
      (node (ref "D8") (pin "3") (pintype "passive"))
      (node (ref "R40") (pin "2") (pinfunction "2_2") (pintype "passive"))
    )
    (net (code "38") (name "Net-(D9-Pad1)") (class "Default")
      (node (ref "D9") (pin "1") (pintype "passive"))
      (node (ref "R41") (pin "2") (pinfunction "2_2") (pintype "passive"))
    )
    (net (code "39") (name "Net-(D9-Pad2)") (class "Default")
      (node (ref "D9") (pin "2") (pintype "passive"))
      (node (ref "R42") (pin "2") (pinfunction "2_2") (pintype "passive"))
    )
    (net (code "40") (name "Net-(D9-Pad3)") (class "Default")
      (node (ref "D9") (pin "3") (pintype "passive"))
      (node (ref "R43") (pin "2") (pinfunction "2_2") (pintype "passive"))
    )
    (net (code "41") (name "Net-(D10-Pad1)") (class "Default")
      (node (ref "D10") (pin "1") (pintype "passive"))
      (node (ref "R44") (pin "2") (pinfunction "2_2") (pintype "passive"))
    )
    (net (code "42") (name "Net-(D10-Pad2)") (class "Default")
      (node (ref "D10") (pin "2") (pintype "passive"))
      (node (ref "R45") (pin "2") (pinfunction "2_2") (pintype "passive"))
    )
    (net (code "43") (name "Net-(D10-Pad3)") (class "Default")
      (node (ref "D10") (pin "3") (pintype "passive"))
      (node (ref "R47") (pin "2") (pinfunction "2_2") (pintype "passive"))
    )
    (net (code "44") (name "Net-(D11-Pad1)") (class "Default")
      (node (ref "D11") (pin "1") (pintype "passive"))
      (node (ref "R48") (pin "2") (pinfunction "2_2") (pintype "passive"))
    )
    (net (code "45") (name "Net-(D11-Pad2)") (class "Default")
      (node (ref "D11") (pin "2") (pintype "passive"))
      (node (ref "R49") (pin "2") (pinfunction "2_2") (pintype "passive"))
    )
    (net (code "46") (name "Net-(D11-Pad3)") (class "Default")
      (node (ref "D11") (pin "3") (pintype "passive"))
      (node (ref "R50") (pin "2") (pinfunction "2_2") (pintype "passive"))
    )
    (net (code "47") (name "Net-(D12-Pad1)") (class "Default")
      (node (ref "D12") (pin "1") (pintype "passive"))
      (node (ref "R51") (pin "2") (pinfunction "2_2") (pintype "passive"))
    )
    (net (code "48") (name "Net-(D12-Pad2)") (class "Default")
      (node (ref "D12") (pin "2") (pintype "passive"))
      (node (ref "R52") (pin "2") (pinfunction "2_2") (pintype "passive"))
    )
    (net (code "49") (name "Net-(D12-Pad3)") (class "Default")
      (node (ref "D12") (pin "3") (pintype "passive"))
      (node (ref "R25") (pin "2") (pinfunction "2_2") (pintype "passive"))
    )
    (net (code "50") (name "Net-(Q3-G)") (class "Default")
      (node (ref "Q3") (pin "1") (pinfunction "G_1") (pintype "passive"))
      (node (ref "R4") (pin "1") (pinfunction "1_1") (pintype "passive"))
    )
    (net (code "51") (name "Net-(Q4-G)") (class "Default")
      (node (ref "Q4") (pin "1") (pinfunction "G_1") (pintype "passive"))
      (node (ref "R19") (pin "1") (pinfunction "1_1") (pintype "passive"))
    )
    (net (code "52") (name "Net-(Q5-G)") (class "Default")
      (node (ref "Q5") (pin "1") (pinfunction "G_1") (pintype "passive"))
      (node (ref "R21") (pin "1") (pinfunction "1_1") (pintype "passive"))
    )
    (net (code "53") (name "Net-(T1-K)") (class "Default")
      (node (ref "F1") (pin "1") (pinfunction "1_1") (pintype "passive"))
      (node (ref "R1") (pin "1") (pinfunction "1_1") (pintype "passive"))
      (node (ref "T1") (pin "2") (pinfunction "K_2") (pintype "passive"))
    )
    (net (code "54") (name "Net-(T2-K)") (class "Default")
      (node (ref "F2") (pin "1") (pinfunction "1_1") (pintype "passive"))
      (node (ref "R5") (pin "1") (pinfunction "1_1") (pintype "passive"))
      (node (ref "T2") (pin "2") (pinfunction "K_2") (pintype "passive"))
    )
    (net (code "55") (name "Net-(U1-CB)") (class "Default")
      (node (ref "C1") (pin "1") (pinfunction "1_1") (pintype "passive"))
      (node (ref "U1") (pin "1") (pinfunction "CB_1") (pintype "passive"))
    )
    (net (code "56") (name "Net-(U1-FB)") (class "Default")
      (node (ref "R11") (pin "2") (pinfunction "2_2") (pintype "passive"))
      (node (ref "R9") (pin "1") (pinfunction "1_1") (pintype "passive"))
      (node (ref "U1") (pin "4") (pinfunction "FB_4") (pintype "passive"))
    )
    (net (code "57") (name "Net-(U2-C2CK{slash}~{RST})") (class "Default")
      (node (ref "P1") (pin "3") (pinfunction "3_3") (pintype "passive"))
      (node (ref "U2") (pin "8") (pinfunction "C2CK/~{RST}_8") (pintype "passive"))
    )
    (net (code "58") (name "Net-(U3A-IN+)") (class "Default")
      (node (ref "C10") (pin "1") (pinfunction "1_1") (pintype "passive"))
      (node (ref "R14") (pin "2") (pinfunction "2_2") (pintype "passive"))
      (node (ref "R15") (pin "1") (pinfunction "1_1") (pintype "passive"))
      (node (ref "U3") (pin "3") (pinfunction "IN+_3") (pintype "input"))
    )
    (net (code "59") (name "Net-(U3A-IN-)") (class "Default")
      (node (ref "R10") (pin "2") (pinfunction "2_2") (pintype "passive"))
      (node (ref "R7") (pin "1") (pinfunction "1_1") (pintype "passive"))
      (node (ref "U3") (pin "2") (pinfunction "IN-_2") (pintype "input"))
    )
    (net (code "60") (name "Net-(U3A-OUT)") (class "Default")
      (node (ref "R3") (pin "1") (pinfunction "1_1") (pintype "passive"))
      (node (ref "R7") (pin "2") (pinfunction "2_2") (pintype "passive"))
      (node (ref "U3") (pin "1") (pinfunction "OUT_1") (pintype "output"))
    )
    (net (code "61") (name "Net-(U3B-IN+)") (class "Default")
      (node (ref "C9") (pin "1") (pinfunction "1_1") (pintype "passive"))
      (node (ref "R15") (pin "2") (pinfunction "2_2") (pintype "passive"))
      (node (ref "R16") (pin "2") (pinfunction "2_2") (pintype "passive"))
      (node (ref "U3") (pin "5") (pinfunction "IN+_5") (pintype "input"))
    )
    (net (code "62") (name "Net-(U3B-IN-)") (class "Default")
      (node (ref "R12") (pin "2") (pinfunction "2_2") (pintype "passive"))
      (node (ref "R2") (pin "1") (pinfunction "1_1") (pintype "passive"))
      (node (ref "U3") (pin "6") (pinfunction "IN-_6") (pintype "input"))
    )
    (net (code "63") (name "Net-(U3B-OUT)") (class "Default")
      (node (ref "R13") (pin "1") (pinfunction "1_1") (pintype "passive"))
      (node (ref "R2") (pin "2") (pinfunction "2_2") (pintype "passive"))
      (node (ref "U3") (pin "7") (pinfunction "OUT_7") (pintype "output"))
    )
    (net (code "64") (name "Net-(U4-BYP)") (class "Default")
      (node (ref "C3") (pin "1") (pinfunction "1_1") (pintype "passive"))
      (node (ref "U4") (pin "4") (pinfunction "BYP_4") (pintype "passive"))
    )
    (net (code "65") (name "Net-(U4-EN)") (class "Default")
      (node (ref "R26") (pin "2") (pinfunction "2_2") (pintype "passive"))
      (node (ref "U4") (pin "3") (pinfunction "EN_3") (pintype "passive"))
    )
    (net (code "66") (name "Net-(U5-A)") (class "Default")
      (node (ref "R5") (pin "2") (pinfunction "2_2") (pintype "passive"))
      (node (ref "U5") (pin "6") (pinfunction "A_6") (pintype "passive"))
    )
    (net (code "67") (name "Net-(U5-B)") (class "Default")
      (node (ref "R1") (pin "2") (pinfunction "2_2") (pintype "passive"))
      (node (ref "U5") (pin "7") (pinfunction "B_7") (pintype "passive"))
    )
    (net (code "68") (name "VDD_+5V") (class "Default")
      (node (ref "C11") (pin "2") (pinfunction "2_2") (pintype "passive"))
      (node (ref "C13") (pin "1") (pinfunction "1_1") (pintype "passive"))
      (node (ref "C2") (pin "1") (pinfunction "1_1") (pintype "passive"))
      (node (ref "L1") (pin "2") (pinfunction "2_2") (pintype "passive"))
      (node (ref "Q3") (pin "2") (pinfunction "S_2") (pintype "passive"))
      (node (ref "Q4") (pin "2") (pinfunction "S_2") (pintype "passive"))
      (node (ref "Q5") (pin "2") (pinfunction "S_2") (pintype "passive"))
      (node (ref "R20") (pin "1") (pinfunction "1_1") (pintype "passive"))
      (node (ref "R22") (pin "1") (pinfunction "1_1") (pintype "passive"))
      (node (ref "R26") (pin "1") (pinfunction "1_1") (pintype "passive"))
      (node (ref "R6") (pin "1") (pinfunction "1_1") (pintype "passive"))
      (node (ref "R9") (pin "2") (pinfunction "2_2") (pintype "passive"))
      (node (ref "U4") (pin "1") (pinfunction "Vin_1") (pintype "passive"))
      (node (ref "U5") (pin "8") (pinfunction "VCC_8") (pintype "passive"))
    )
    (net (code "69") (name "unconnected-(U1-ON{slash}OFF-Pad5)") (class "Default")
      (node (ref "U1") (pin "5") (pinfunction "ON/OFF_5") (pintype "passive+no_connect"))
    )
    (net (code "70") (name "unconnected-(U3A-VCC-Pad8)") (class "Default")
      (node (ref "U3") (pin "8") (pinfunction "VCC_8") (pintype "power_in+no_connect"))
    )
    (net (code "71") (name "unconnected-(U3A-VEE-Pad4)") (class "Default")
      (node (ref "U3") (pin "4") (pinfunction "VEE_4") (pintype "power_in+no_connect"))
    )
  )
)
